# 34063.net
KiCad netlist of a schematic drawn in EAGLE
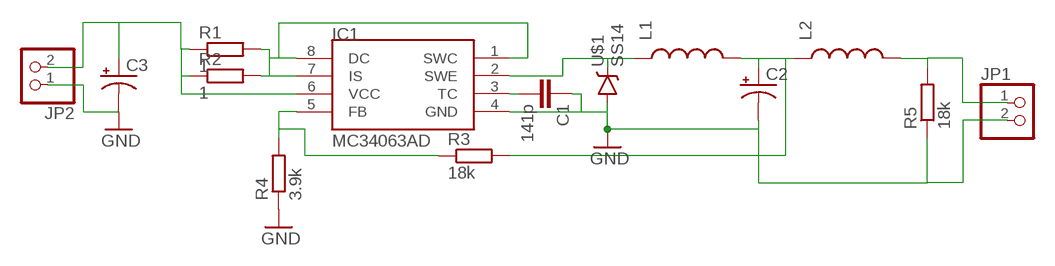
[diagram p0: schematic, sheet 1]

(export (version "E")
  (design (tool "Eeschema 10.0.6"))
  (components
    (comp (ref "C1")
      (value "141p")
      (footprint "eagle-import:C0603")
      (libsource (lib "eagle-import") (part "CC0603"))
    )
    (comp (ref "C2")
      (value "CAP_POLE")
      (footprint "eagle-import:PANASONIC_E")
      (libsource (lib "eagle-import") (part "CAP_POLE"))
    )
    (comp (ref "C3")
      (value "CAP_POLE")
      (footprint "eagle-import:PANASONIC_E")
      (libsource (lib "eagle-import") (part "CAP_POLE"))
    )
    (comp (ref "IC1")
      (value "MC34063AD")
      (footprint "eagle-import:SOIC8")
      (libsource (lib "eagle-import") (part "MC34063AD"))
    )
    (comp (ref "JP1")
      (value "PINHD-1X02_2.54")
      (footprint "eagle-import:1X02")
      (libsource (lib "eagle-import") (part "PINHD-1X02_2.54"))
    )
    (comp (ref "JP2")
      (value "PINHD-1X02_2.54")
      (footprint "eagle-import:1X02")
      (libsource (lib "eagle-import") (part "PINHD-1X02_2.54"))
    )
    (comp (ref "L1")
      (value "INDUCTORSRU1038")
      (footprint "eagle-import:SRU1038")
      (libsource (lib "eagle-import") (part "INDUCTORSRU1038"))
    )
    (comp (ref "L2")
      (value "INDUCTORVLF4012A")
      (footprint "eagle-import:VLF4012A")
      (libsource (lib "eagle-import") (part "INDUCTORVLF4012A"))
    )
    (comp (ref "R1")
      (value "1")
      (footprint "eagle-import:R0805")
      (libsource (lib "eagle-import") (part "R0805"))
    )
    (comp (ref "R2")
      (value "1")
      (footprint "eagle-import:R0805")
      (libsource (lib "eagle-import") (part "R0805"))
    )
    (comp (ref "R3")
      (value "18k")
      (footprint "eagle-import:R0805")
      (libsource (lib "eagle-import") (part "R0805"))
    )
    (comp (ref "R4")
      (value "3.9k")
      (footprint "eagle-import:R0805")
      (libsource (lib "eagle-import") (part "R0805"))
    )
    (comp (ref "R5")
      (value "18k")
      (footprint "eagle-import:R0805")
      (libsource (lib "eagle-import") (part "R0805"))
    )
    (comp (ref "U$1")
      (value "SS14")
      (footprint "eagle-import:SMA-DIODE")
      (libsource (lib "eagle-import") (part "SS14"))
    )
  )
  (nets
    (net (code "1") (name "GND") (class "Default")
      (node (ref "C1") (pin "1") (pinfunction "1_1") (pintype "passive"))
      (node (ref "C2") (pin "-") (pinfunction "-_-") (pintype "passive"))
      (node (ref "C3") (pin "-") (pinfunction "-_-") (pintype "passive"))
      (node (ref "IC1") (pin "4") (pinfunction "GND_4") (pintype "passive"))
      (node (ref "JP1") (pin "2") (pinfunction "2_2") (pintype "passive"))
      (node (ref "JP2") (pin "1") (pinfunction "1_1") (pintype "passive"))
      (node (ref "R4") (pin "1") (pinfunction "1_1") (pintype "passive"))
      (node (ref "R5") (pin "1") (pinfunction "1_1") (pintype "passive"))
      (node (ref "U$1") (pin "A") (pinfunction "A_A") (pintype "passive"))
    )
    (net (code "2") (name "Net-(IC1-DC)") (class "Default")
      (node (ref "IC1") (pin "1") (pinfunction "SWC_1") (pintype "passive"))
      (node (ref "IC1") (pin "7") (pinfunction "IS_7") (pintype "passive"))
      (node (ref "IC1") (pin "8") (pinfunction "DC_8") (pintype "passive"))
      (node (ref "R1") (pin "2") (pinfunction "2_2") (pintype "passive"))
      (node (ref "R2") (pin "2") (pinfunction "2_2") (pintype "passive"))
    )
    (net (code "3") (name "Net-(IC1-FB)") (class "Default")
      (node (ref "IC1") (pin "5") (pinfunction "FB_5") (pintype "passive"))
      (node (ref "R3") (pin "1") (pinfunction "1_1") (pintype "passive"))
      (node (ref "R4") (pin "2") (pinfunction "2_2") (pintype "passive"))
    )
    (net (code "4") (name "Net-(IC1-SWE)") (class "Default")
      (node (ref "IC1") (pin "2") (pinfunction "SWE_2") (pintype "passive"))
      (node (ref "L1") (pin "1") (pinfunction "1_1") (pintype "passive"))
      (node (ref "U$1") (pin "C") (pinfunction "C_C") (pintype "passive"))
    )
    (net (code "5") (name "Net-(IC1-TC)") (class "Default")
      (node (ref "C1") (pin "2") (pinfunction "2_2") (pintype "passive"))
      (node (ref "IC1") (pin "3") (pinfunction "TC_3") (pintype "passive"))
    )
    (net (code "6") (name "Net-(IC1-VCC)") (class "Default")
      (node (ref "C3") (pin "+") (pinfunction "+_+") (pintype "passive"))
      (node (ref "IC1") (pin "6") (pinfunction "VCC_6") (pintype "passive"))
      (node (ref "JP2") (pin "2") (pinfunction "2_2") (pintype "passive"))
      (node (ref "R1") (pin "1") (pinfunction "1_1") (pintype "passive"))
      (node (ref "R2") (pin "1") (pinfunction "1_1") (pintype "passive"))
    )
    (net (code "7") (name "Net-(L2-1)") (class "Default")
      (node (ref "C2") (pin "+") (pinfunction "+_+") (pintype "passive"))
      (node (ref "L1") (pin "2") (pinfunction "2_2") (pintype "passive"))
      (node (ref "L2") (pin "P$1") (pinfunction "1_P$1") (pintype "passive"))
      (node (ref "R3") (pin "2") (pinfunction "2_2") (pintype "passive"))
    )
    (net (code "8") (name "Net-(L2-2)") (class "Default")
      (node (ref "JP1") (pin "1") (pinfunction "1_1") (pintype "passive"))
      (node (ref "L2") (pin "P$2") (pinfunction "2_P$2") (pintype "passive"))
      (node (ref "R5") (pin "2") (pinfunction "2_2") (pintype "passive"))
    )
  )
)
